# Flash.net
KiCad netlist of a schematic drawn in Altium Designer
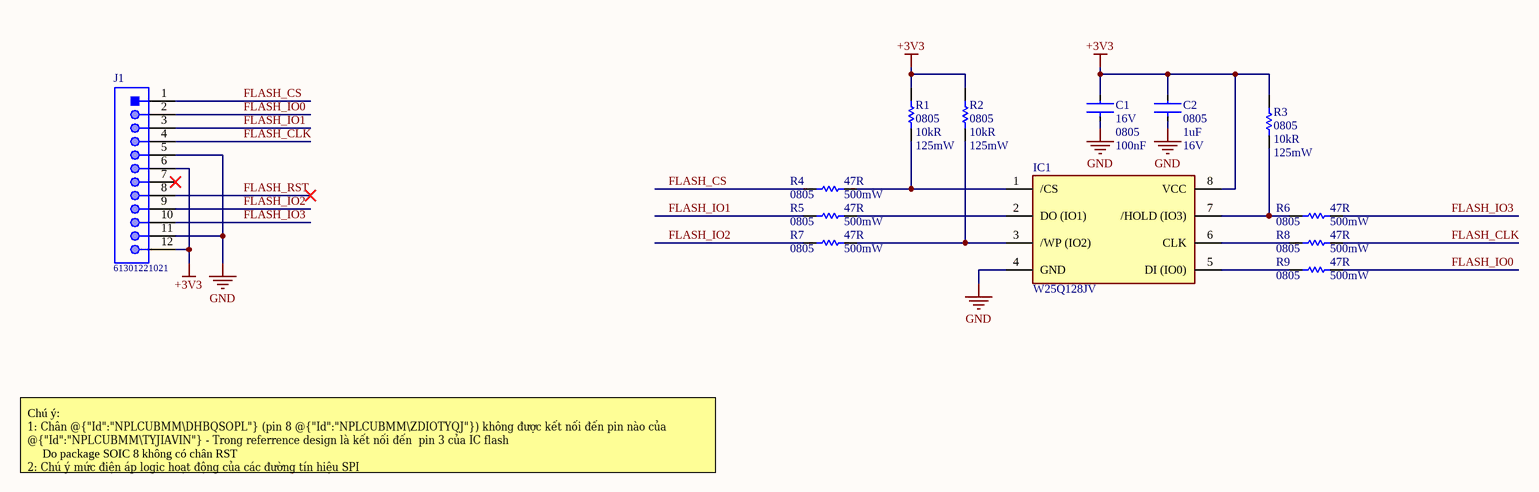
[diagram p0: Flash.SchDoc]

(export (version "E")
  (design (tool "Eeschema 10.0.6"))
  (components
    (comp (ref "C1")
      (value "08051C104KAT2A")
      (footprint "FP-0805-L_2_01_0_2-W_1_25-IPC_B")
      (description "General Purpose Ceramic Capacitor, 0805, 100nF, 10%, X7R, 15%, 100V")
      (fields
        (field (name "VOLTAGE RATING") "16V")
        (field (name "CASE CODE (IMPERIAL)") "0805")
        (field (name "CAPACITANCE") "100nF")
        (field (name "VOLTAGE") "100V")
        (field (name "TOLERANCE") "10%")
      )
      (libsource (lib "Altium Content Vault") (part "b4654b650e69147ec39a6b967a45e02"))
    )
    (comp (ref "C2")
      (value "1uF")
      (footprint "FP-0805-L_2_01_0_2-W_1_25-IPC_B")
      (description "General Purpose Ceramic Capacitor, 0805, 100nF, 10%, X7R, 15%, 100V")
      (fields
        (field (name "MANUFACTURER") "KEMET")
        (field (name "MANUFACTURER PART NUMBER") "C0805C105K4PACTU")
        (field (name "CASE/PACKAGE") "0805")
        (field (name "VOLTAGE RATING") "16V")
      )
      (libsource (lib "Altium Content Vault") (part "b4654b650e69147ec39a6b967a45e02"))
    )
    (comp (ref "IC1")
      (value "W25Q128JV")
      (footprint "SamacSys:SOIC127P790X216-8N")
      (description "Integrated Circuit")
      (fields
        (field (name "MANUFACTURER_PART_NUMBER") "W25Q128JVSIM TR")
        (field (name "MOUSER PART NUMBER") "454-W25Q128JVSIMTR")
      )
      (libsource (lib "Flash Pmod") (part "W25Q128JVSIM_TR"))
    )
    (comp (ref "J1")
      (value "61301221021")
      (footprint "61301221021")
      (description "THT Angled Pin Header WR-PHD, Pitch 2.54 mm, Dual Row, 12 pins")
      (fields (field (name "MANUFACTURER") "Wurth Electronics") (field (name "PUBLISHER") "WurthElektronik"))
      (libsource (lib "Flash Pmod") (part "CMP-1502-01087-1"))
    )
    (comp (ref "R1")
      (value "10kR")
      (footprint "RESC2013X70X40LL20T20")
      (description "10 kOhms ±1% 0.125W, 1/8W Chip Resistor 0805 (2012 Metric) Moisture Resistant Thick Film")
      (fields
        (field (name "MANUFACTURER") "Yageo")
        (field (name "MANUFACTURER PART NUMBER") "RC0805FR-0710KL")
        (field (name "CASE/PACKAGE") "0805")
        (field (name "POWER RATING") "125mW")
      )
      (libsource (lib "Altium Content Vault") (part "RES"))
    )
    (comp (ref "R2")
      (value "10kR")
      (footprint "RESC2013X70X40LL20T20")
      (description "10 kOhms ±1% 0.125W, 1/8W Chip Resistor 0805 (2012 Metric) Moisture Resistant Thick Film")
      (fields
        (field (name "MANUFACTURER") "Yageo")
        (field (name "MANUFACTURER PART NUMBER") "RC0805FR-0710KL")
        (field (name "CASE/PACKAGE") "0805")
        (field (name "POWER RATING") "125mW")
      )
      (libsource (lib "Altium Content Vault") (part "RES"))
    )
    (comp (ref "R3")
      (value "10kR")
      (footprint "RESC2013X70X40LL20T20")
      (description "10 kOhms ±1% 0.125W, 1/8W Chip Resistor 0805 (2012 Metric) Moisture Resistant Thick Film")
      (fields
        (field (name "MANUFACTURER") "Yageo")
        (field (name "MANUFACTURER PART NUMBER") "RC0805FR-0710KL")
        (field (name "CASE/PACKAGE") "0805")
        (field (name "POWER RATING") "125mW")
      )
      (libsource (lib "Altium Content Vault") (part "RES"))
    )
    (comp (ref "R4")
      (value "47R")
      (footprint "RESC2013X70X40LL20T20")
      (fields
        (field (name "MANUFACTURER") "Panasonic")
        (field (name "MANUFACTURER PART NUMBER") "ERJ-P6WF47R0V")
        (field (name "CASE CODE (IMPERIAL)") "0805")
        (field (name "TOLERANCE") "1%")
        (field (name "POWER RATING") "500mW")
      )
      (libsource (lib "Altium Content Vault") (part "RES"))
    )
    (comp (ref "R5")
      (value "47R")
      (footprint "RESC2013X70X40LL20T20")
      (fields
        (field (name "MANUFACTURER") "Panasonic")
        (field (name "MANUFACTURER PART NUMBER") "ERJ-P6WF47R0V")
        (field (name "CASE CODE (IMPERIAL)") "0805")
        (field (name "TOLERANCE") "1%")
        (field (name "POWER RATING") "500mW")
      )
      (libsource (lib "Altium Content Vault") (part "RES"))
    )
    (comp (ref "R6")
      (value "47R")
      (footprint "RESC2013X70X40LL20T20")
      (fields
        (field (name "MANUFACTURER") "Panasonic")
        (field (name "MANUFACTURER PART NUMBER") "ERJ-P6WF47R0V")
        (field (name "CASE CODE (IMPERIAL)") "0805")
        (field (name "TOLERANCE") "1%")
        (field (name "POWER RATING") "500mW")
      )
      (libsource (lib "Altium Content Vault") (part "RES"))
    )
    (comp (ref "R7")
      (value "47R")
      (footprint "RESC2013X70X40LL20T20")
      (fields
        (field (name "MANUFACTURER") "Panasonic")
        (field (name "MANUFACTURER PART NUMBER") "ERJ-P6WF47R0V")
        (field (name "CASE CODE (IMPERIAL)") "0805")
        (field (name "TOLERANCE") "1%")
        (field (name "POWER RATING") "500mW")
      )
      (libsource (lib "Altium Content Vault") (part "RES"))
    )
    (comp (ref "R8")
      (value "47R")
      (footprint "RESC2013X70X40LL20T20")
      (fields
        (field (name "MANUFACTURER") "Panasonic")
        (field (name "MANUFACTURER PART NUMBER") "ERJ-P6WF47R0V")
        (field (name "CASE CODE (IMPERIAL)") "0805")
        (field (name "TOLERANCE") "1%")
        (field (name "POWER RATING") "500mW")
      )
      (libsource (lib "Altium Content Vault") (part "RES"))
    )
    (comp (ref "R9")
      (value "47R")
      (footprint "RESC2013X70X40LL20T20")
      (fields
        (field (name "MANUFACTURER") "Panasonic")
        (field (name "MANUFACTURER PART NUMBER") "ERJ-P6WF47R0V")
        (field (name "CASE CODE (IMPERIAL)") "0805")
        (field (name "TOLERANCE") "1%")
        (field (name "POWER RATING") "500mW")
      )
      (libsource (lib "Altium Content Vault") (part "RES"))
    )
  )
  (nets
    (net (code "1") (name "+3V3") (class "Default")
      (node (ref "C1") (pin "2") (pinfunction "2_2") (pintype "passive"))
      (node (ref "C2") (pin "2") (pinfunction "2_2") (pintype "passive"))
      (node (ref "IC1") (pin "8") (pinfunction "VCC_8") (pintype "passive"))
      (node (ref "J1") (pin "12") (pinfunction "12_12") (pintype "passive"))
      (node (ref "J1") (pin "6") (pinfunction "6_6") (pintype "passive"))
      (node (ref "R1") (pin "1") (pinfunction "1_1") (pintype "passive"))
      (node (ref "R2") (pin "1") (pinfunction "1_1") (pintype "passive"))
      (node (ref "R3") (pin "1") (pinfunction "1_1") (pintype "passive"))
    )
    (net (code "2") (name "/FLASH_CLK") (class "Default")
      (node (ref "J1") (pin "4") (pinfunction "4_4") (pintype "passive"))
      (node (ref "R8") (pin "1") (pinfunction "1_1") (pintype "passive"))
    )
    (net (code "3") (name "/FLASH_CS") (class "Default")
      (node (ref "J1") (pin "1") (pinfunction "1_1") (pintype "passive"))
      (node (ref "R4") (pin "2") (pinfunction "2_2") (pintype "passive"))
    )
    (net (code "4") (name "/FLASH_IO0") (class "Default")
      (node (ref "J1") (pin "2") (pinfunction "2_2") (pintype "passive"))
      (node (ref "R9") (pin "1") (pinfunction "1_1") (pintype "passive"))
    )
    (net (code "5") (name "/FLASH_IO1") (class "Default")
      (node (ref "J1") (pin "3") (pinfunction "3_3") (pintype "passive"))
      (node (ref "R5") (pin "2") (pinfunction "2_2") (pintype "passive"))
    )
    (net (code "6") (name "/FLASH_IO2") (class "Default")
      (node (ref "J1") (pin "9") (pinfunction "9_9") (pintype "passive"))
      (node (ref "R7") (pin "2") (pinfunction "2_2") (pintype "passive"))
    )
    (net (code "7") (name "/FLASH_IO3") (class "Default")
      (node (ref "J1") (pin "10") (pinfunction "10_10") (pintype "passive"))
      (node (ref "R6") (pin "1") (pinfunction "1_1") (pintype "passive"))
    )
    (net (code "8") (name "/FLASH_RST") (class "Default")
      (node (ref "J1") (pin "8") (pinfunction "8_8") (pintype "passive+no_connect"))
    )
    (net (code "9") (name "GND") (class "Default")
      (node (ref "C1") (pin "1") (pinfunction "1_1") (pintype "passive"))
      (node (ref "C2") (pin "1") (pinfunction "1_1") (pintype "passive"))
      (node (ref "IC1") (pin "4") (pinfunction "GND_4") (pintype "passive"))
      (node (ref "J1") (pin "11") (pinfunction "11_11") (pintype "passive"))
      (node (ref "J1") (pin "5") (pinfunction "5_5") (pintype "passive"))
    )
    (net (code "10") (name "Net-(IC1-CLK)") (class "Default")
      (node (ref "IC1") (pin "6") (pinfunction "CLK_6") (pintype "passive"))
      (node (ref "R8") (pin "2") (pinfunction "2_2") (pintype "passive"))
    )
    (net (code "11") (name "Net-(IC1-DI_(IO0))") (class "Default")
      (node (ref "IC1") (pin "5") (pinfunction "DI_(IO0)_5") (pintype "passive"))
      (node (ref "R9") (pin "2") (pinfunction "2_2") (pintype "passive"))
    )
    (net (code "12") (name "Net-(IC1-DO_(IO1))") (class "Default")
      (node (ref "IC1") (pin "2") (pinfunction "DO_(IO1)_2") (pintype "passive"))
      (node (ref "R5") (pin "1") (pinfunction "1_1") (pintype "passive"))
    )
    (net (code "13") (name "Net-(IC1-{slash}CS)") (class "Default")
      (node (ref "IC1") (pin "1") (pinfunction "/CS_1") (pintype "passive"))
      (node (ref "R1") (pin "2") (pinfunction "2_2") (pintype "passive"))
      (node (ref "R4") (pin "1") (pinfunction "1_1") (pintype "passive"))
    )
    (net (code "14") (name "Net-(IC1-{slash}HOLD_(IO3))") (class "Default")
      (node (ref "IC1") (pin "7") (pinfunction "/HOLD_(IO3)_7") (pintype "passive"))
      (node (ref "R3") (pin "2") (pinfunction "2_2") (pintype "passive"))
      (node (ref "R6") (pin "2") (pinfunction "2_2") (pintype "passive"))
    )
    (net (code "15") (name "Net-(IC1-{slash}WP_(IO2))") (class "Default")
      (node (ref "IC1") (pin "3") (pinfunction "/WP_(IO2)_3") (pintype "passive"))
      (node (ref "R2") (pin "2") (pinfunction "2_2") (pintype "passive"))
      (node (ref "R7") (pin "1") (pinfunction "1_1") (pintype "passive"))
    )
    (net (code "16") (name "unconnected-(J1-Pad7)") (class "Default")
      (node (ref "J1") (pin "7") (pinfunction "7_7") (pintype "passive+no_connect"))
    )
  )
)
